# CAN.net
KiCad netlist of a schematic drawn in Altium Designer
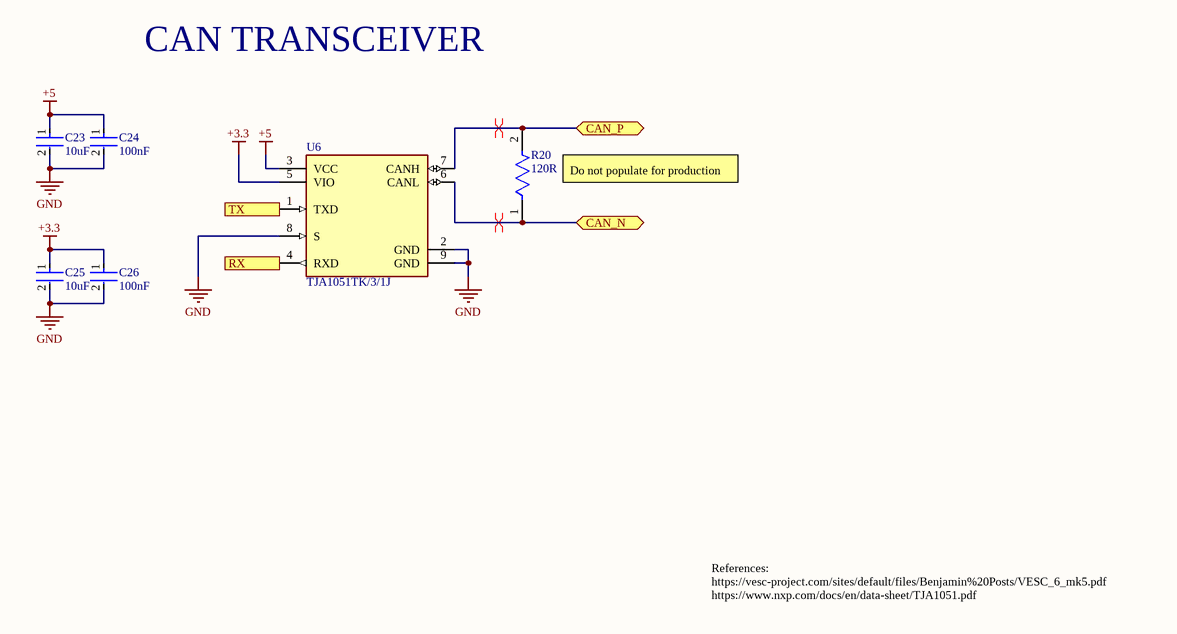
[diagram p0: CAN.SchDoc]

(export (version "E")
  (design (tool "Eeschema 10.0.6"))
  (components
    (comp (ref "C23")
      (value "10uF")
      (footprint "FP-CC0805-0_85-MFG")
      (description "10uF 25V X5R ±10% 0805 Multilayer Ceramic Capacitors MLCC - SMD/SMT ROHS")
      (fields
        (field (name "MANUFACTURER") "Yageo Group")
        (field (name "MANUFACTURER PART NUMBER") "CC0402KRX7R9BB682")
      )
      (libsource (lib "BEESC_Lib") (part "CL21A106KAYNNNE"))
    )
    (comp (ref "C24")
      (value "100nF")
      (footprint "FP-CC0402-MFG")
      (description "100nF 50V X7R ±10% 0402 Multilayer Ceramic Capacitors MLCC - SMD/SMT ROHS")
      (fields
        (field (name "MANUFACTURER") "Yageo Group")
        (field (name "MANUFACTURER PART NUMBER") "CC0402KRX7R9BB682")
      )
      (libsource (lib "BEESC_Lib") (part "CL05B104KB54PNC"))
    )
    (comp (ref "C25")
      (value "10uF")
      (footprint "FP-CC0805-0_85-MFG")
      (description "10uF 25V X5R ±10% 0805 Multilayer Ceramic Capacitors MLCC - SMD/SMT ROHS")
      (fields
        (field (name "MANUFACTURER") "Yageo Group")
        (field (name "MANUFACTURER PART NUMBER") "CC0402KRX7R9BB682")
      )
      (libsource (lib "BEESC_Lib") (part "CL21A106KAYNNNE"))
    )
    (comp (ref "C26")
      (value "100nF")
      (footprint "FP-CC0402-MFG")
      (description "100nF 50V X7R ±10% 0402 Multilayer Ceramic Capacitors MLCC - SMD/SMT ROHS")
      (fields
        (field (name "MANUFACTURER") "Yageo Group")
        (field (name "MANUFACTURER PART NUMBER") "CC0402KRX7R9BB682")
      )
      (libsource (lib "BEESC_Lib") (part "CL05B104KB54PNC"))
    )
    (comp (ref "R20")
      (value "120R")
      (footprint "FP-AC0402-MFG")
      (libsource (lib "BEESC_Lib") (part "0402WGF1200TCE"))
    )
    (comp (ref "U6")
      (value "TJA1051TK/3/1J")
      (footprint "FP-SOT782-1-MFG")
      (description "-40℃~+150℃ 4.5V~5.5V 5Mbps 70mA CAN Transceiver HVSON-8-EP(3x3) CAN Transceivers ROHS")
      (libsource (lib "BEESC_Lib") (part "TJA1051TK/3/1J"))
    )
  )
  (nets
    (net (code "1") (name "+3.3") (class "Default")
      (node (ref "C25") (pin "1") (pinfunction "1_1") (pintype "passive"))
      (node (ref "C26") (pin "1") (pinfunction "1_1") (pintype "passive"))
      (node (ref "U6") (pin "5") (pinfunction "VIO_5") (pintype "power_in"))
    )
    (net (code "2") (name "+5") (class "Default")
      (node (ref "C23") (pin "1") (pinfunction "1_1") (pintype "passive"))
      (node (ref "C24") (pin "1") (pinfunction "1_1") (pintype "passive"))
      (node (ref "U6") (pin "3") (pinfunction "VCC_3") (pintype "power_in"))
    )
    (net (code "3") (name "/CAN_N") (class "Default")
      (node (ref "R20") (pin "1") (pinfunction "1_1") (pintype "passive"))
      (node (ref "U6") (pin "6") (pinfunction "CANL_6") (pintype "bidirectional"))
    )
    (net (code "4") (name "/CAN_P") (class "Default")
      (node (ref "R20") (pin "2") (pinfunction "2_2") (pintype "passive"))
      (node (ref "U6") (pin "7") (pinfunction "CANH_7") (pintype "bidirectional"))
    )
    (net (code "5") (name "/RX") (class "Default")
      (node (ref "U6") (pin "4") (pinfunction "RXD_4") (pintype "output"))
    )
    (net (code "6") (name "/TX") (class "Default")
      (node (ref "U6") (pin "1") (pinfunction "TXD_1") (pintype "input"))
    )
    (net (code "7") (name "GND") (class "Default")
      (node (ref "C23") (pin "2") (pinfunction "2_2") (pintype "passive"))
      (node (ref "C24") (pin "2") (pinfunction "2_2") (pintype "passive"))
      (node (ref "C25") (pin "2") (pinfunction "2_2") (pintype "passive"))
      (node (ref "C26") (pin "2") (pinfunction "2_2") (pintype "passive"))
      (node (ref "U6") (pin "2") (pinfunction "GND_2") (pintype "power_in"))
      (node (ref "U6") (pin "8") (pinfunction "S_8") (pintype "input"))
      (node (ref "U6") (pin "9") (pinfunction "GND_9") (pintype "power_in"))
    )
  )
)
